# Sheet1.net
KiCad netlist of a schematic drawn in Altium Designer
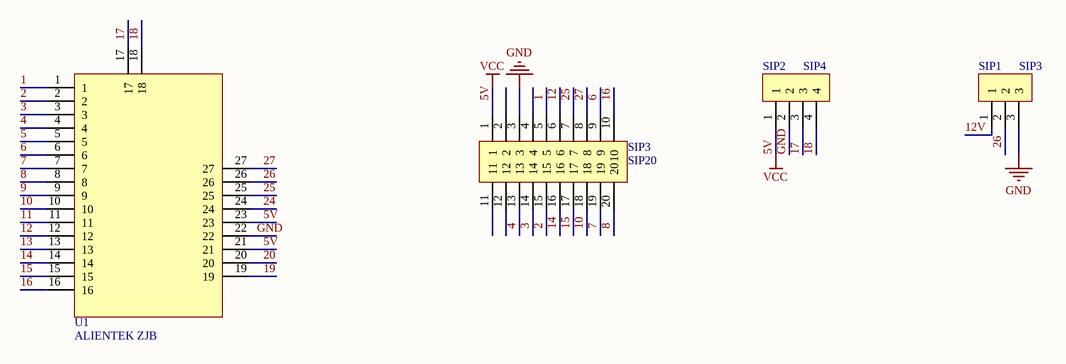
[diagram p0: Sheet1.SchDoc]

(export (version "E")
  (design (tool "Eeschema 10.0.6"))
  (components
    (comp (ref "SIP1") (value "SIP3") (footprint "SIP3") (libsource (lib "Schlib1") (part "SIP3")))
    (comp (ref "SIP2") (value "SIP4") (footprint "SIP4") (libsource (lib "Schlib1") (part "SIP4")))
    (comp (ref "SIP3") (value "SIP20") (footprint "SIP20") (libsource (lib "Schlib1") (part "SIP20")))
    (comp (ref "U1")
      (value "ALIENTEK ZJB")
      (footprint "ALIENTEK ZJB")
      (libsource (lib "Schlib1") (part "ALIENTEK ZJB"))
    )
  )
  (nets
    (net (code "1") (name "/1") (class "Default")
      (node (ref "SIP3") (pin "5") (pinfunction "5_5") (pintype "passive"))
      (node (ref "U1") (pin "1") (pinfunction "1_1") (pintype "passive"))
    )
    (net (code "2") (name "/2") (class "Default")
      (node (ref "SIP3") (pin "15") (pinfunction "15_15") (pintype "passive"))
      (node (ref "U1") (pin "2") (pinfunction "2_2") (pintype "passive"))
    )
    (net (code "3") (name "/3") (class "Default")
      (node (ref "SIP3") (pin "14") (pinfunction "14_14") (pintype "passive"))
      (node (ref "U1") (pin "3") (pinfunction "3_3") (pintype "passive"))
    )
    (net (code "4") (name "/4") (class "Default")
      (node (ref "SIP3") (pin "13") (pinfunction "13_13") (pintype "passive"))
      (node (ref "U1") (pin "4") (pinfunction "4_4") (pintype "passive"))
    )
    (net (code "5") (name "/5") (class "Default")
      (node (ref "U1") (pin "5") (pinfunction "5_5") (pintype "passive"))
    )
    (net (code "6") (name "/6") (class "Default")
      (node (ref "SIP3") (pin "9") (pinfunction "9_9") (pintype "passive"))
      (node (ref "U1") (pin "6") (pinfunction "6_6") (pintype "passive"))
    )
    (net (code "7") (name "/7") (class "Default")
      (node (ref "SIP3") (pin "19") (pinfunction "19_19") (pintype "passive"))
      (node (ref "U1") (pin "7") (pinfunction "7_7") (pintype "passive"))
    )
    (net (code "8") (name "/8") (class "Default")
      (node (ref "SIP3") (pin "20") (pinfunction "20_20") (pintype "passive"))
      (node (ref "U1") (pin "8") (pinfunction "8_8") (pintype "passive"))
    )
    (net (code "9") (name "/9") (class "Default")
      (node (ref "U1") (pin "9") (pinfunction "9_9") (pintype "passive"))
    )
    (net (code "10") (name "/10") (class "Default")
      (node (ref "SIP3") (pin "18") (pinfunction "18_18") (pintype "passive"))
      (node (ref "U1") (pin "10") (pinfunction "10_10") (pintype "passive"))
    )
    (net (code "11") (name "/11") (class "Default")
      (node (ref "U1") (pin "11") (pinfunction "11_11") (pintype "passive"))
    )
    (net (code "12") (name "/12") (class "Default")
      (node (ref "SIP3") (pin "6") (pinfunction "6_6") (pintype "passive"))
      (node (ref "U1") (pin "12") (pinfunction "12_12") (pintype "passive"))
    )
    (net (code "13") (name "/12V") (class "Default")
      (node (ref "SIP1") (pin "1") (pinfunction "1_1") (pintype "passive"))
    )
    (net (code "14") (name "/13") (class "Default")
      (node (ref "U1") (pin "13") (pinfunction "13_13") (pintype "passive"))
    )
    (net (code "15") (name "/14") (class "Default")
      (node (ref "SIP3") (pin "16") (pinfunction "16_16") (pintype "passive"))
      (node (ref "U1") (pin "14") (pinfunction "14_14") (pintype "passive"))
    )
    (net (code "16") (name "/15") (class "Default")
      (node (ref "SIP3") (pin "17") (pinfunction "17_17") (pintype "passive"))
      (node (ref "U1") (pin "15") (pinfunction "15_15") (pintype "passive"))
    )
    (net (code "17") (name "/16") (class "Default")
      (node (ref "SIP3") (pin "10") (pinfunction "10_10") (pintype "passive"))
      (node (ref "U1") (pin "16") (pinfunction "16_16") (pintype "passive"))
    )
    (net (code "18") (name "/17") (class "Default")
      (node (ref "SIP2") (pin "3") (pinfunction "3_3") (pintype "passive"))
      (node (ref "U1") (pin "17") (pinfunction "17_17") (pintype "passive"))
    )
    (net (code "19") (name "/18") (class "Default")
      (node (ref "SIP2") (pin "4") (pinfunction "4_4") (pintype "passive"))
      (node (ref "U1") (pin "18") (pinfunction "18_18") (pintype "passive"))
    )
    (net (code "20") (name "/19") (class "Default")
      (node (ref "U1") (pin "19") (pinfunction "19_19") (pintype "passive"))
    )
    (net (code "21") (name "/20") (class "Default")
      (node (ref "U1") (pin "20") (pinfunction "20_20") (pintype "passive"))
    )
    (net (code "22") (name "/24") (class "Default")
      (node (ref "U1") (pin "24") (pinfunction "24_24") (pintype "passive"))
    )
    (net (code "23") (name "/25") (class "Default")
      (node (ref "SIP3") (pin "7") (pinfunction "7_7") (pintype "passive"))
      (node (ref "U1") (pin "25") (pinfunction "25_25") (pintype "passive"))
    )
    (net (code "24") (name "/26") (class "Default")
      (node (ref "SIP1") (pin "2") (pinfunction "2_2") (pintype "passive"))
      (node (ref "U1") (pin "26") (pinfunction "26_26") (pintype "passive"))
    )
    (net (code "25") (name "/27") (class "Default")
      (node (ref "SIP3") (pin "8") (pinfunction "8_8") (pintype "passive"))
      (node (ref "U1") (pin "27") (pinfunction "27_27") (pintype "passive"))
    )
    (net (code "26") (name "GND") (class "Default")
      (node (ref "SIP1") (pin "3") (pinfunction "3_3") (pintype "passive"))
      (node (ref "SIP2") (pin "2") (pinfunction "2_2") (pintype "passive"))
      (node (ref "SIP3") (pin "3") (pinfunction "3_3") (pintype "passive"))
      (node (ref "U1") (pin "22") (pinfunction "22_22") (pintype "passive"))
    )
    (net (code "27") (name "VCC") (class "Default")
      (node (ref "SIP2") (pin "1") (pinfunction "1_1") (pintype "passive"))
      (node (ref "SIP3") (pin "1") (pinfunction "1_1") (pintype "passive"))
      (node (ref "U1") (pin "21") (pinfunction "21_21") (pintype "passive"))
      (node (ref "U1") (pin "23") (pinfunction "23_23") (pintype "passive"))
    )
    (net (code "28") (name "unconnected-(SIP3-Pad2)") (class "Default")
      (node (ref "SIP3") (pin "2") (pinfunction "2_2") (pintype "passive"))
    )
    (net (code "29") (name "unconnected-(SIP3-Pad4)") (class "Default")
      (node (ref "SIP3") (pin "4") (pinfunction "4_4") (pintype "passive"))
    )
    (net (code "30") (name "unconnected-(SIP3-Pad11)") (class "Default")
      (node (ref "SIP3") (pin "11") (pinfunction "11_11") (pintype "passive"))
    )
    (net (code "31") (name "unconnected-(SIP3-Pad12)") (class "Default")
      (node (ref "SIP3") (pin "12") (pinfunction "12_12") (pintype "passive"))
    )
  )
)
